# routed.net
KiCad netlist of a schematic drawn in Altium Designer
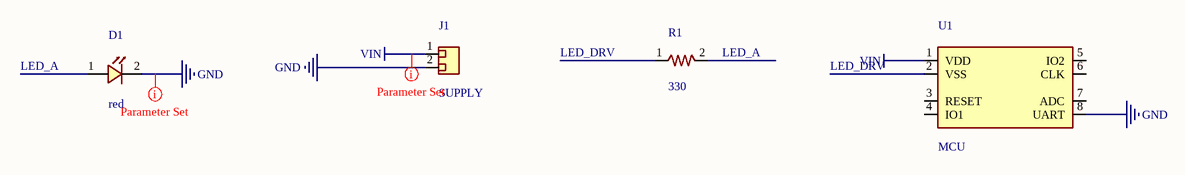
[diagram p0: routed.SchDoc]

(export (version "E")
  (design (tool "Eeschema 10.0.6"))
  (components
    (comp (ref "D1")
      (value "red")
      (footprint "routed:LED0603_Kingbright_APT1608SURCK")
      (libsource (lib "routed") (part "LED"))
    )
    (comp (ref "J1")
      (value "SUPPLY")
      (footprint "routed:Header_1x2_P2.54")
      (libsource (lib "routed") (part "Connector_2"))
    )
    (comp (ref "R1")
      (value "330")
      (footprint "routed:Chip_0603")
      (libsource (lib "routed") (part "Resistor"))
    )
    (comp (ref "U1")
      (value "MCU")
      (footprint "routed:DIP8_Microchip_P")
      (libsource (lib "routed") (part "Microcontroller"))
    )
  )
  (nets
    (net (code "1") (name "/LED_A") (class "Default")
      (node (ref "D1") (pin "1") (pinfunction "A_1") (pintype "passive"))
      (node (ref "R1") (pin "2") (pinfunction "B_2") (pintype "passive"))
    )
    (net (code "2") (name "/LED_DRV") (class "Default")
      (node (ref "R1") (pin "1") (pinfunction "A_1") (pintype "passive"))
      (node (ref "U1") (pin "2") (pinfunction "VSS_2") (pintype "passive"))
    )
    (net (code "3") (name "GND") (class "Default")
      (node (ref "D1") (pin "2") (pinfunction "K_2") (pintype "passive"))
      (node (ref "J1") (pin "2") (pinfunction "Passive_2") (pintype "passive"))
      (node (ref "U1") (pin "8") (pinfunction "UART_8") (pintype "passive"))
    )
    (net (code "4") (name "VIN") (class "Default")
      (node (ref "J1") (pin "1") (pinfunction "Passive_1") (pintype "passive"))
      (node (ref "U1") (pin "1") (pinfunction "VDD_1") (pintype "passive"))
    )
    (net (code "5") (name "unconnected-(U1-ADC-Pad7)") (class "Default")
      (node (ref "U1") (pin "7") (pinfunction "ADC_7") (pintype "passive"))
    )
    (net (code "6") (name "unconnected-(U1-CLK-Pad6)") (class "Default")
      (node (ref "U1") (pin "6") (pinfunction "CLK_6") (pintype "passive"))
    )
    (net (code "7") (name "unconnected-(U1-IO1-Pad4)") (class "Default")
      (node (ref "U1") (pin "4") (pinfunction "IO1_4") (pintype "passive"))
    )
    (net (code "8") (name "unconnected-(U1-IO2-Pad5)") (class "Default")
      (node (ref "U1") (pin "5") (pinfunction "IO2_5") (pintype "passive"))
    )
    (net (code "9") (name "unconnected-(U1-RESET-Pad3)") (class "Default")
      (node (ref "U1") (pin "3") (pinfunction "RESET_3") (pintype "passive"))
    )
  )
)
